# Polarshield_v2_4.net
KiCad netlist of a schematic drawn in EAGLE
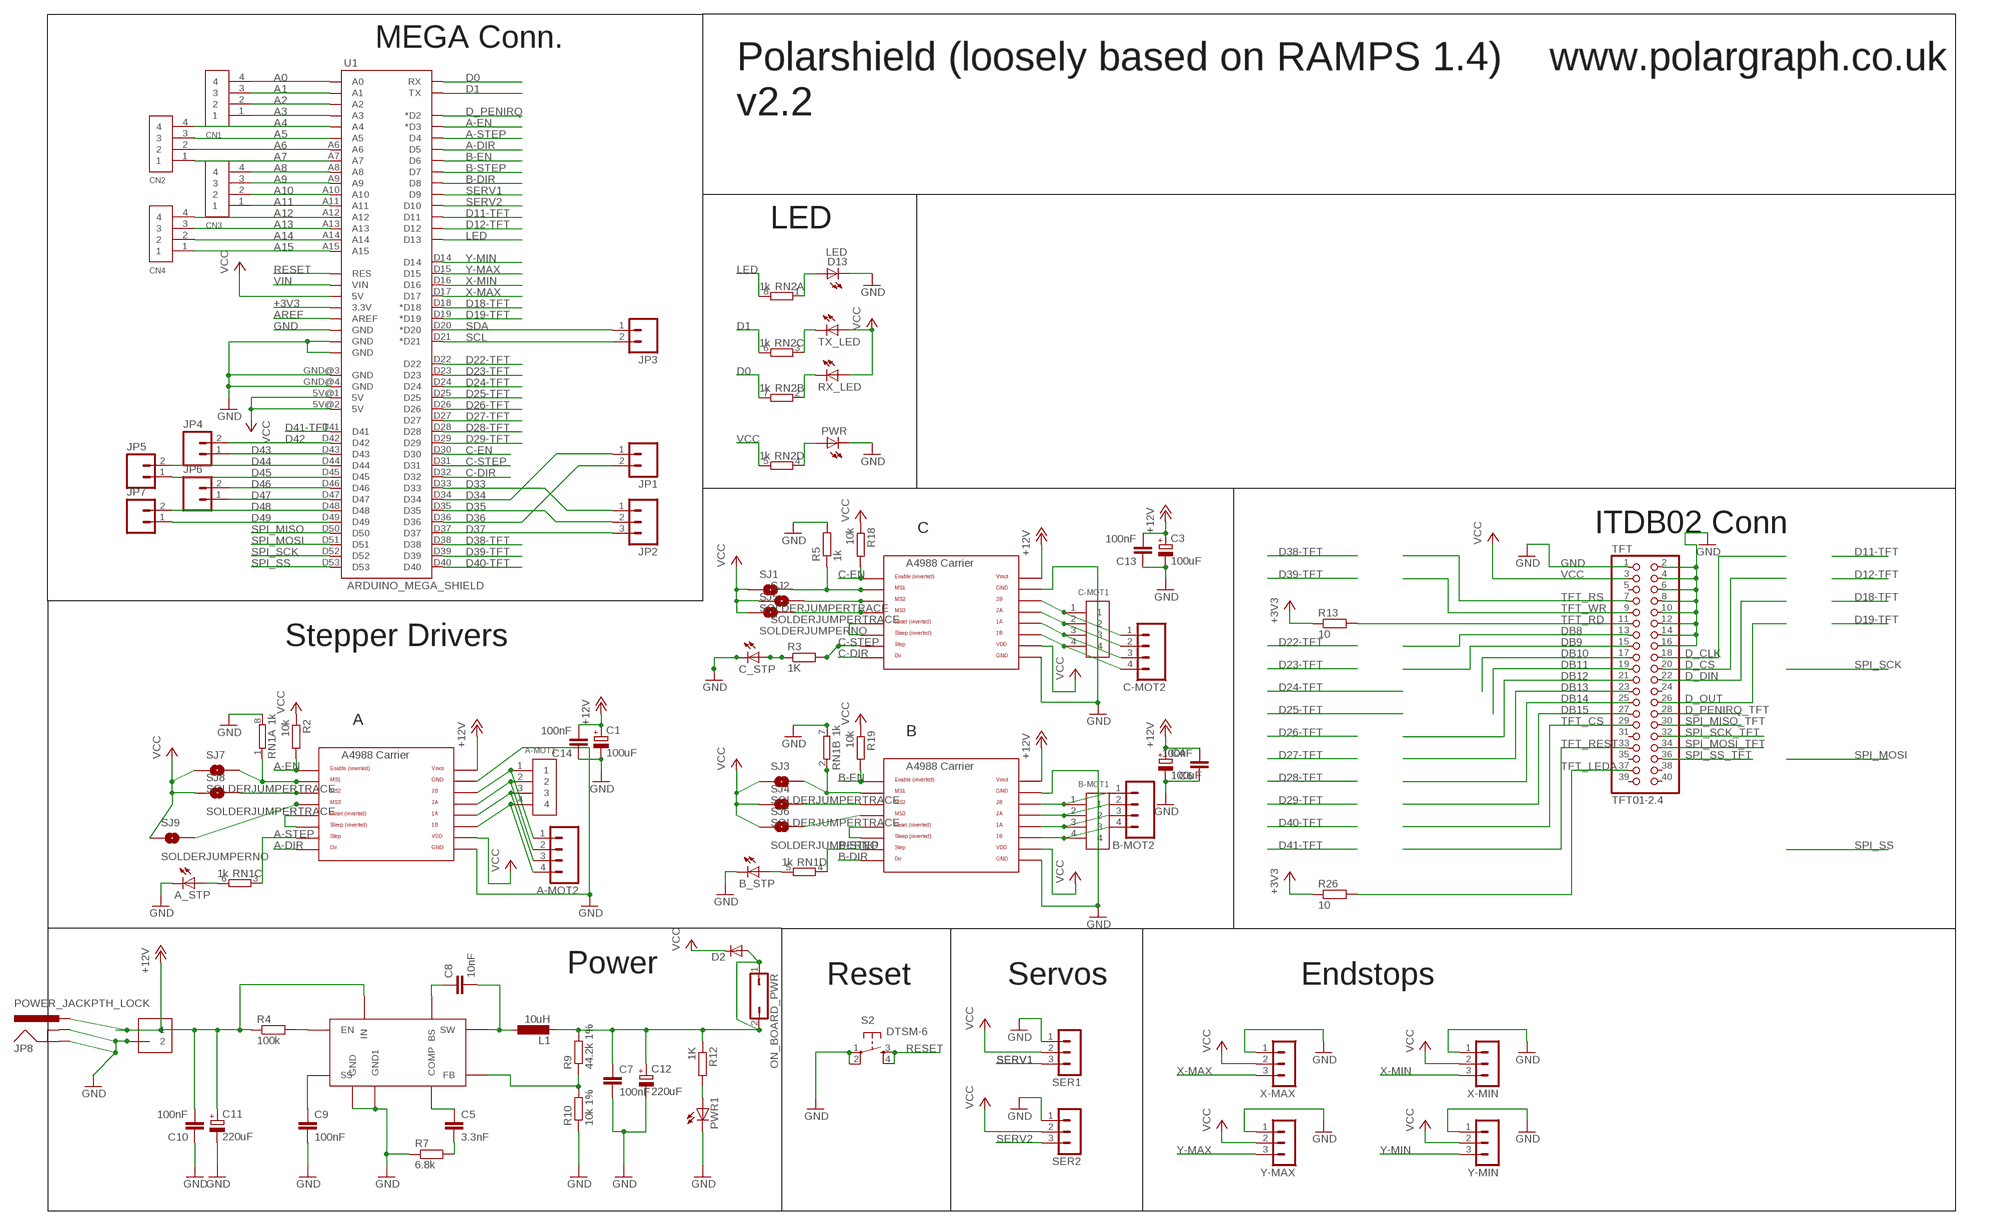
[diagram p0: schematic, sheet 1, part 1 of 2]
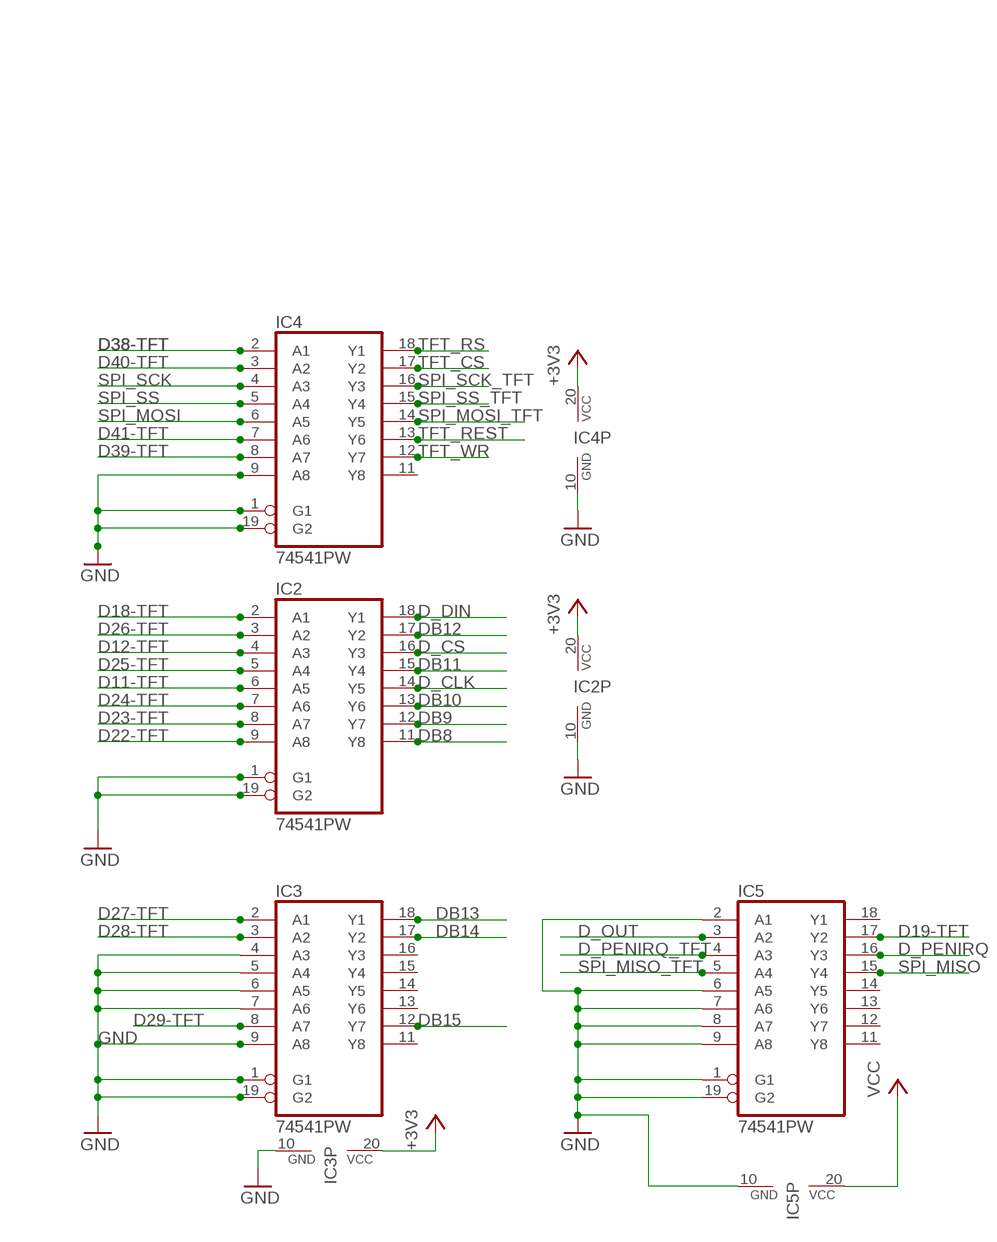
[diagram p1: schematic, sheet 1, part 2 of 2]

(export (version "E")
  (design (tool "Eeschema 10.0.6"))
  (components
    (comp (ref "A-MOT1")
      (value "1X4-BIG")
      (footprint "eagle-import:1X04-BIG")
      (libsource (lib "eagle-import") (part "adafruit_1X4-BIG"))
    )
    (comp (ref "A-MOT2")
      (value "M04SCREW")
      (footprint "eagle-import:SCREWTERMINAL-3.5MM-4")
      (libsource (lib "eagle-import") (part "M04SCREW"))
    )
    (comp (ref "A_STP")
      (value "LEDCHIP-LED0805")
      (footprint "eagle-import:CHIP-LED0805")
      (libsource (lib "eagle-import") (part "LEDCHIP-LED0805"))
    )
    (comp (ref "B-MOT1")
      (value "1X4-BIG")
      (footprint "eagle-import:1X04-BIG")
      (libsource (lib "eagle-import") (part "adafruit_1X4-BIG"))
    )
    (comp (ref "B-MOT2")
      (value "M04SCREW")
      (footprint "eagle-import:SCREWTERMINAL-3.5MM-4")
      (libsource (lib "eagle-import") (part "M04SCREW"))
    )
    (comp (ref "B_STP")
      (value "LEDCHIP-LED0805")
      (footprint "eagle-import:CHIP-LED0805")
      (libsource (lib "eagle-import") (part "LEDCHIP-LED0805"))
    )
    (comp (ref "C-MOT1")
      (value "1X4-BIG")
      (footprint "eagle-import:1X04-BIG")
      (libsource (lib "eagle-import") (part "adafruit_1X4-BIG"))
    )
    (comp (ref "C-MOT2")
      (value "M04SCREW")
      (footprint "eagle-import:SCREWTERMINAL-3.5MM-4")
      (libsource (lib "eagle-import") (part "M04SCREW"))
    )
    (comp (ref "C1")
      (value "100uF")
      (footprint "eagle-import:153CLV-0605")
      (libsource (lib "eagle-import") (part "CPOL-EU153CLV-0605"))
    )
    (comp (ref "C3")
      (value "100uF")
      (footprint "eagle-import:153CLV-0605")
      (libsource (lib "eagle-import") (part "CPOL-EU153CLV-0605"))
    )
    (comp (ref "C4")
      (value "100uF")
      (footprint "eagle-import:153CLV-0605")
      (libsource (lib "eagle-import") (part "CPOL-EU153CLV-0605"))
    )
    (comp (ref "C5")
      (value "3.3nF")
      (footprint "eagle-import:C0805K")
      (libsource (lib "eagle-import") (part "C-EUC0805K"))
    )
    (comp (ref "C6")
      (value "100nF")
      (footprint "eagle-import:C0805")
      (libsource (lib "eagle-import") (part "C-EUC0805"))
    )
    (comp (ref "C7")
      (value "100nF")
      (footprint "eagle-import:C0805K")
      (libsource (lib "eagle-import") (part "C-EUC0805K"))
    )
    (comp (ref "C8")
      (value "10nF")
      (footprint "eagle-import:C0805K")
      (libsource (lib "eagle-import") (part "C-EUC0805K"))
    )
    (comp (ref "C9")
      (value "100nF")
      (footprint "eagle-import:C0805K")
      (libsource (lib "eagle-import") (part "C-EUC0805K"))
    )
    (comp (ref "C10")
      (value "100nF")
      (footprint "eagle-import:C0805K")
      (libsource (lib "eagle-import") (part "C-EUC0805K"))
    )
    (comp (ref "C11")
      (value "220uF")
      (footprint "eagle-import:153CLV-0807")
      (libsource (lib "eagle-import") (part "resistor_CPOL-EU153CLV-0807"))
    )
    (comp (ref "C12")
      (value "220uF")
      (footprint "eagle-import:153CLV-0807")
      (libsource (lib "eagle-import") (part "resistor_CPOL-EU153CLV-0807"))
    )
    (comp (ref "C13")
      (value "100nF")
      (footprint "eagle-import:C0805")
      (libsource (lib "eagle-import") (part "C-EUC0805"))
    )
    (comp (ref "C14")
      (value "100nF")
      (footprint "eagle-import:C0805")
      (libsource (lib "eagle-import") (part "C-EUC0805"))
    )
    (comp (ref "CN1")
      (value "1X4-CLEANBIG")
      (footprint "eagle-import:1X04-CLEANBIG")
      (libsource (lib "eagle-import") (part "1X4-CLEANBIG"))
    )
    (comp (ref "CN2")
      (value "1X4-CLEANBIG")
      (footprint "eagle-import:1X04-CLEANBIG")
      (libsource (lib "eagle-import") (part "1X4-CLEANBIG"))
    )
    (comp (ref "CN3")
      (value "1X4-CLEANBIG")
      (footprint "eagle-import:1X04-CLEANBIG")
      (libsource (lib "eagle-import") (part "1X4-CLEANBIG"))
    )
    (comp (ref "CN4")
      (value "1X4-CLEANBIG")
      (footprint "eagle-import:1X04-CLEANBIG")
      (libsource (lib "eagle-import") (part "1X4-CLEANBIG"))
    )
    (comp (ref "C_STP")
      (value "LEDCHIP-LED0805")
      (footprint "eagle-import:CHIP-LED0805")
      (libsource (lib "eagle-import") (part "LEDCHIP-LED0805"))
    )
    (comp (ref "D2")
      (value "DIODE-DO214BA")
      (footprint "eagle-import:DO214BA")
      (libsource (lib "eagle-import") (part "DIODE-DO214BA"))
    )
    (comp (ref "D13")
      (value "LED")
      (footprint "eagle-import:CHIP-LED0805")
      (libsource (lib "eagle-import") (part "LEDCHIP-LED0805"))
    )
    (comp (ref "IC1")
      (value "MP2307")
      (footprint "eagle-import:SOIC8")
      (libsource (lib "eagle-import") (part "MP2307"))
    )
    (comp (ref "IC2")
      (value "74541PW")
      (footprint "eagle-import:TSSOP20")
      (libsource (lib "eagle-import") (part "74541PW"))
    )
    (comp (ref "IC3")
      (value "74541PW")
      (footprint "eagle-import:TSSOP20")
      (libsource (lib "eagle-import") (part "74541PW"))
    )
    (comp (ref "IC4")
      (value "74541PW")
      (footprint "eagle-import:TSSOP20")
      (libsource (lib "eagle-import") (part "74541PW"))
    )
    (comp (ref "IC5")
      (value "74541PW")
      (footprint "eagle-import:TSSOP20")
      (libsource (lib "eagle-import") (part "74541PW"))
    )
    (comp (ref "J1")
      (value "1X2-3.5MM")
      (footprint "eagle-import:1X2-3.5MM")
      (libsource (lib "eagle-import") (part "1X2-3.5MM"))
    )
    (comp (ref "JP1")
      (value "M021X02_NO_SILK")
      (footprint "eagle-import:1X02_NO_SILK")
      (libsource (lib "eagle-import") (part "M021X02_NO_SILK"))
    )
    (comp (ref "JP2")
      (value "M031X03_NO_SILK")
      (footprint "eagle-import:1X03_NO_SILK")
      (libsource (lib "eagle-import") (part "M031X03_NO_SILK"))
    )
    (comp (ref "JP3")
      (value "M021X02_NO_SILK")
      (footprint "eagle-import:1X02_NO_SILK")
      (libsource (lib "eagle-import") (part "M021X02_NO_SILK"))
    )
    (comp (ref "JP4")
      (value "M021X02_NO_SILK")
      (footprint "eagle-import:1X02_NO_SILK")
      (libsource (lib "eagle-import") (part "M021X02_NO_SILK"))
    )
    (comp (ref "JP5")
      (value "M021X02_NO_SILK")
      (footprint "eagle-import:1X02_NO_SILK")
      (libsource (lib "eagle-import") (part "M021X02_NO_SILK"))
    )
    (comp (ref "JP6")
      (value "M021X02_NO_SILK")
      (footprint "eagle-import:1X02_NO_SILK")
      (libsource (lib "eagle-import") (part "M021X02_NO_SILK"))
    )
    (comp (ref "JP7")
      (value "M021X02_NO_SILK")
      (footprint "eagle-import:1X02_NO_SILK")
      (libsource (lib "eagle-import") (part "M021X02_NO_SILK"))
    )
    (comp (ref "JP8")
      (value "POWER_JACKPTH_LOCK")
      (footprint "eagle-import:POWER_JACK_PTH_LOCK")
      (libsource (lib "eagle-import") (part "POWER_JACKPTH_LOCK"))
    )
    (comp (ref "L1")
      (value "10uH")
      (footprint "eagle-import:PIS2816")
      (libsource (lib "eagle-import") (part "L-EUPIS2816"))
    )
    (comp (ref "ON_BOARD_PWR")
      (value "JP1Q")
      (footprint "eagle-import:JP1")
      (libsource (lib "eagle-import") (part "JP1Q"))
    )
    (comp (ref "PWR")
      (value "LEDCHIP-LED0805")
      (footprint "eagle-import:CHIP-LED0805")
      (libsource (lib "eagle-import") (part "LEDCHIP-LED0805"))
    )
    (comp (ref "PWR1")
      (value "LEDCHIP-LED0805")
      (footprint "eagle-import:CHIP-LED0805")
      (libsource (lib "eagle-import") (part "LEDCHIP-LED0805"))
    )
    (comp (ref "R2")
      (value "10k")
      (footprint "eagle-import:R0805")
      (libsource (lib "eagle-import") (part "R-EU_R0805"))
    )
    (comp (ref "R3")
      (value "1K")
      (footprint "eagle-import:R0805")
      (libsource (lib "eagle-import") (part "R-EU_R0805"))
    )
    (comp (ref "R4")
      (value "100k")
      (footprint "eagle-import:R0805")
      (libsource (lib "eagle-import") (part "resistor_R-EU_R0805"))
    )
    (comp (ref "R5")
      (value "1k")
      (footprint "eagle-import:R0805")
      (libsource (lib "eagle-import") (part "R-EU_R0805"))
    )
    (comp (ref "R7")
      (value "6.8k")
      (footprint "eagle-import:R0805")
      (libsource (lib "eagle-import") (part "resistor_R-EU_R0805"))
    )
    (comp (ref "R9")
      (value "44.2k 1%")
      (footprint "eagle-import:R0805")
      (libsource (lib "eagle-import") (part "resistor_R-EU_R0805"))
    )
    (comp (ref "R10")
      (value "10k 1%")
      (footprint "eagle-import:R0805")
      (libsource (lib "eagle-import") (part "resistor_R-EU_R0805"))
    )
    (comp (ref "R12")
      (value "1K")
      (footprint "eagle-import:R0805")
      (libsource (lib "eagle-import") (part "R-EU_R0805"))
    )
    (comp (ref "R13")
      (value "10")
      (footprint "eagle-import:R0805")
      (libsource (lib "eagle-import") (part "resistor_R-EU_R0805"))
    )
    (comp (ref "R18")
      (value "10k")
      (footprint "eagle-import:R0805")
      (libsource (lib "eagle-import") (part "R-EU_R0805"))
    )
    (comp (ref "R19")
      (value "10k")
      (footprint "eagle-import:R0805")
      (libsource (lib "eagle-import") (part "R-EU_R0805"))
    )
    (comp (ref "R26")
      (value "10")
      (footprint "eagle-import:R0805")
      (libsource (lib "eagle-import") (part "resistor_R-EU_R0805"))
    )
    (comp (ref "RN1")
      (value "1k")
      (footprint "eagle-import:EXBN8V")
      (libsource (lib "eagle-import") (part "4R-NEXBN8V"))
    )
    (comp (ref "RN2")
      (value "1k")
      (footprint "eagle-import:EXBN8V")
      (libsource (lib "eagle-import") (part "4R-NEXBN8V"))
    )
    (comp (ref "RX_LED")
      (value "LEDCHIP-LED0805")
      (footprint "eagle-import:CHIP-LED0805")
      (libsource (lib "eagle-import") (part "LEDCHIP-LED0805"))
    )
    (comp (ref "S2")
      (value "DTSM-6")
      (footprint "eagle-import:DTSM-6")
      (libsource (lib "eagle-import") (part "DTSM-6"))
    )
    (comp (ref "SER1")
      (value "3PIN-HEADER")
      (footprint "eagle-import:3PIN-HEADER")
      (libsource (lib "eagle-import") (part "3PIN-HEADER"))
    )
    (comp (ref "SER2")
      (value "3PIN-HEADER")
      (footprint "eagle-import:3PIN-HEADER")
      (libsource (lib "eagle-import") (part "3PIN-HEADER"))
    )
    (comp (ref "SJ1")
      (value "SOLDERJUMPERTRACE")
      (footprint "eagle-import:SJ_2S-TRACE")
      (libsource (lib "eagle-import") (part "SOLDERJUMPERTRACE"))
    )
    (comp (ref "SJ2")
      (value "SOLDERJUMPERTRACE")
      (footprint "eagle-import:SJ_2S-TRACE")
      (libsource (lib "eagle-import") (part "SOLDERJUMPERTRACE"))
    )
    (comp (ref "SJ3")
      (value "SOLDERJUMPERTRACE")
      (footprint "eagle-import:SJ_2S-TRACE")
      (libsource (lib "eagle-import") (part "SOLDERJUMPERTRACE"))
    )
    (comp (ref "SJ4")
      (value "SOLDERJUMPERTRACE")
      (footprint "eagle-import:SJ_2S-TRACE")
      (libsource (lib "eagle-import") (part "SOLDERJUMPERTRACE"))
    )
    (comp (ref "SJ5")
      (value "SOLDERJUMPERNO")
      (footprint "eagle-import:SJ_2S-NO")
      (libsource (lib "eagle-import") (part "SOLDERJUMPERNO"))
    )
    (comp (ref "SJ6")
      (value "SOLDERJUMPERNO")
      (footprint "eagle-import:SJ_2S-NO")
      (libsource (lib "eagle-import") (part "SOLDERJUMPERNO"))
    )
    (comp (ref "SJ7")
      (value "SOLDERJUMPERTRACE")
      (footprint "eagle-import:SJ_2S-TRACE")
      (libsource (lib "eagle-import") (part "SOLDERJUMPERTRACE"))
    )
    (comp (ref "SJ8")
      (value "SOLDERJUMPERTRACE")
      (footprint "eagle-import:SJ_2S-TRACE")
      (libsource (lib "eagle-import") (part "SOLDERJUMPERTRACE"))
    )
    (comp (ref "SJ9")
      (value "SOLDERJUMPERNO")
      (footprint "eagle-import:SJ_2S-NO")
      (libsource (lib "eagle-import") (part "SOLDERJUMPERNO"))
    )
    (comp (ref "TFT")
      (value "TFT01-2.4")
      (footprint "eagle-import:TFT01-2.4")
      (libsource (lib "eagle-import") (part "TFT01-2.4"))
    )
    (comp (ref "TX_LED")
      (value "LEDCHIP-LED0805")
      (footprint "eagle-import:CHIP-LED0805")
      (libsource (lib "eagle-import") (part "LEDCHIP-LED0805"))
    )
    (comp (ref "U$1")
      (value "A4988BREAKOUT")
      (footprint "eagle-import:A4988BREAKOUT")
      (libsource (lib "eagle-import") (part "A4988BREAKOUT"))
    )
    (comp (ref "U$6")
      (value "A4988BREAKOUT")
      (footprint "eagle-import:A4988BREAKOUT")
      (libsource (lib "eagle-import") (part "A4988BREAKOUT"))
    )
    (comp (ref "U$7")
      (value "A4988BREAKOUT")
      (footprint "eagle-import:A4988BREAKOUT")
      (libsource (lib "eagle-import") (part "A4988BREAKOUT"))
    )
    (comp (ref "U1")
      (value "ARDUINO_MEGA_SHIELD")
      (footprint "eagle-import:ARDUINO_MEGA_SHIELD")
      (libsource (lib "eagle-import") (part "ARDUINO_MEGA_SHIELD"))
    )
    (comp (ref "X-MAX")
      (value "3PIN-HEADER")
      (footprint "eagle-import:3PIN-HEADER")
      (libsource (lib "eagle-import") (part "3PIN-HEADER"))
    )
    (comp (ref "X-MIN")
      (value "3PIN-HEADER")
      (footprint "eagle-import:3PIN-HEADER")
      (libsource (lib "eagle-import") (part "3PIN-HEADER"))
    )
    (comp (ref "Y-MAX")
      (value "3PIN-HEADER")
      (footprint "eagle-import:3PIN-HEADER")
      (libsource (lib "eagle-import") (part "3PIN-HEADER"))
    )
    (comp (ref "Y-MIN")
      (value "3PIN-HEADER")
      (footprint "eagle-import:3PIN-HEADER")
      (libsource (lib "eagle-import") (part "3PIN-HEADER"))
    )
  )
  (nets
    (net (code "1") (name "+3V3") (class "Default")
      (node (ref "IC2") (pin "20") (pinfunction "VCC_20") (pintype "power_in"))
      (node (ref "IC3") (pin "20") (pinfunction "VCC_20") (pintype "power_in"))
      (node (ref "IC4") (pin "20") (pinfunction "VCC_20") (pintype "power_in"))
      (node (ref "R13") (pin "1") (pinfunction "1_1") (pintype "passive"))
      (node (ref "R26") (pin "1") (pinfunction "1_1") (pintype "passive"))
      (node (ref "U1") (pin "3.3V") (pinfunction "3.3V_3.3V") (pintype "bidirectional"))
    )
    (net (code "2") (name "+12V") (class "Default")
      (node (ref "C1") (pin "+") (pinfunction "+_+") (pintype "passive"))
      (node (ref "C10") (pin "2") (pinfunction "2_2") (pintype "passive"))
      (node (ref "C11") (pin "+") (pinfunction "+_+") (pintype "passive"))
      (node (ref "C13") (pin "2") (pinfunction "2_2") (pintype "passive"))
      (node (ref "C14") (pin "2") (pinfunction "2_2") (pintype "passive"))
      (node (ref "C3") (pin "+") (pinfunction "+_+") (pintype "passive"))
      (node (ref "C4") (pin "+") (pinfunction "+_+") (pintype "passive"))
      (node (ref "C6") (pin "2") (pinfunction "2_2") (pintype "passive"))
      (node (ref "IC1") (pin "IN") (pinfunction "IN_IN") (pintype "bidirectional"))
      (node (ref "J1") (pin "1") (pinfunction "1_1") (pintype "passive"))
      (node (ref "JP8") (pin "PWR") (pinfunction "PWR_PWR") (pintype "bidirectional"))
      (node (ref "R4") (pin "1") (pinfunction "1_1") (pintype "passive"))
      (node (ref "U$1") (pin "VMOT") (pinfunction "VMOT_VMOT") (pintype "power_in"))
      (node (ref "U$6") (pin "VMOT") (pinfunction "VMOT_VMOT") (pintype "power_in"))
      (node (ref "U$7") (pin "VMOT") (pinfunction "VMOT_VMOT") (pintype "power_in"))
    )
    (net (code "3") (name "/A-DIR") (class "Default")
      (node (ref "U$1") (pin "DIR") (pinfunction "DIR_DIR") (pintype "input"))
      (node (ref "U1") (pin "D5") (pinfunction "D5_D5") (pintype "bidirectional"))
    )
    (net (code "4") (name "/A-EN") (class "Default")
      (node (ref "R2") (pin "2") (pinfunction "2_2") (pintype "passive"))
      (node (ref "U$1") (pin "EN") (pinfunction "EN_EN") (pintype "input"))
      (node (ref "U1") (pin "D3") (pinfunction "*D3_D3") (pintype "bidirectional"))
    )
    (net (code "5") (name "/A-STEP") (class "Default")
      (node (ref "RN1") (pin "3") (pinfunction "1_3") (pintype "passive"))
      (node (ref "U$1") (pin "STEP") (pinfunction "STEP_STEP") (pintype "input"))
      (node (ref "U1") (pin "D4") (pinfunction "D4_D4") (pintype "bidirectional"))
    )
    (net (code "6") (name "/A0") (class "Default")
      (node (ref "CN1") (pin "4") (pinfunction "4_4") (pintype "bidirectional"))
      (node (ref "U1") (pin "A0") (pinfunction "A0_A0") (pintype "bidirectional"))
    )
    (net (code "7") (name "/A1") (class "Default")
      (node (ref "CN1") (pin "3") (pinfunction "3_3") (pintype "bidirectional"))
      (node (ref "U1") (pin "A1") (pinfunction "A1_A1") (pintype "bidirectional"))
    )
    (net (code "8") (name "/A2") (class "Default")
      (node (ref "CN1") (pin "2") (pinfunction "2_2") (pintype "bidirectional"))
      (node (ref "U1") (pin "A2") (pinfunction "A2_A2") (pintype "bidirectional"))
    )
    (net (code "9") (name "/A3") (class "Default")
      (node (ref "CN1") (pin "1") (pinfunction "1_1") (pintype "bidirectional"))
      (node (ref "U1") (pin "A3") (pinfunction "A3_A3") (pintype "bidirectional"))
    )
    (net (code "10") (name "/A4") (class "Default")
      (node (ref "CN2") (pin "4") (pinfunction "4_4") (pintype "bidirectional"))
      (node (ref "U1") (pin "A4") (pinfunction "A4_A4") (pintype "bidirectional"))
    )
    (net (code "11") (name "/A5") (class "Default")
      (node (ref "CN2") (pin "3") (pinfunction "3_3") (pintype "bidirectional"))
      (node (ref "U1") (pin "A5") (pinfunction "A5_A5") (pintype "bidirectional"))
    )
    (net (code "12") (name "/A6") (class "Default")
      (node (ref "CN2") (pin "2") (pinfunction "2_2") (pintype "bidirectional"))
      (node (ref "U1") (pin "A6") (pinfunction "A6_A6") (pintype "bidirectional"))
    )
    (net (code "13") (name "/A7") (class "Default")
      (node (ref "CN2") (pin "1") (pinfunction "1_1") (pintype "bidirectional"))
      (node (ref "U1") (pin "A7") (pinfunction "A7_A7") (pintype "bidirectional"))
    )
    (net (code "14") (name "/A8") (class "Default")
      (node (ref "CN3") (pin "4") (pinfunction "4_4") (pintype "bidirectional"))
      (node (ref "U1") (pin "A8") (pinfunction "A8_A8") (pintype "bidirectional"))
    )
    (net (code "15") (name "/A9") (class "Default")
      (node (ref "CN3") (pin "3") (pinfunction "3_3") (pintype "bidirectional"))
      (node (ref "U1") (pin "A9") (pinfunction "A9_A9") (pintype "bidirectional"))
    )
    (net (code "16") (name "/A10") (class "Default")
      (node (ref "CN3") (pin "2") (pinfunction "2_2") (pintype "bidirectional"))
      (node (ref "U1") (pin "A10") (pinfunction "A10_A10") (pintype "bidirectional"))
    )
    (net (code "17") (name "/A11") (class "Default")
      (node (ref "CN3") (pin "1") (pinfunction "1_1") (pintype "bidirectional"))
      (node (ref "U1") (pin "A11") (pinfunction "A11_A11") (pintype "bidirectional"))
    )
    (net (code "18") (name "/A12") (class "Default")
      (node (ref "CN4") (pin "4") (pinfunction "4_4") (pintype "bidirectional"))
      (node (ref "U1") (pin "A12") (pinfunction "A12_A12") (pintype "bidirectional"))
    )
    (net (code "19") (name "/A13") (class "Default")
      (node (ref "CN4") (pin "3") (pinfunction "3_3") (pintype "bidirectional"))
      (node (ref "U1") (pin "A13") (pinfunction "A13_A13") (pintype "bidirectional"))
    )
    (net (code "20") (name "/A14") (class "Default")
      (node (ref "CN4") (pin "2") (pinfunction "2_2") (pintype "bidirectional"))
      (node (ref "U1") (pin "A14") (pinfunction "A14_A14") (pintype "bidirectional"))
    )
    (net (code "21") (name "/A15") (class "Default")
      (node (ref "CN4") (pin "1") (pinfunction "1_1") (pintype "bidirectional"))
      (node (ref "U1") (pin "A15") (pinfunction "A15_A15") (pintype "bidirectional"))
    )
    (net (code "22") (name "/AREF") (class "Default")
      (node (ref "U1") (pin "AREF") (pinfunction "AREF_AREF") (pintype "bidirectional"))
    )
    (net (code "23") (name "/B-DIR") (class "Default")
      (node (ref "U$7") (pin "DIR") (pinfunction "DIR_DIR") (pintype "input"))
      (node (ref "U1") (pin "D8") (pinfunction "D8_D8") (pintype "bidirectional"))
    )
    (net (code "24") (name "/B-EN") (class "Default")
      (node (ref "R19") (pin "2") (pinfunction "2_2") (pintype "passive"))
      (node (ref "U$7") (pin "EN") (pinfunction "EN_EN") (pintype "input"))
      (node (ref "U1") (pin "D6") (pinfunction "D6_D6") (pintype "bidirectional"))
    )
    (net (code "25") (name "/B-STEP") (class "Default")
      (node (ref "RN1") (pin "4") (pinfunction "1_4") (pintype "passive"))
      (node (ref "U$7") (pin "STEP") (pinfunction "STEP_STEP") (pintype "input"))
      (node (ref "U1") (pin "D7") (pinfunction "D7_D7") (pintype "bidirectional"))
    )
    (net (code "26") (name "/C-DIR") (class "Default")
      (node (ref "U$6") (pin "DIR") (pinfunction "DIR_DIR") (pintype "input"))
      (node (ref "U1") (pin "D32") (pinfunction "D32_D32") (pintype "bidirectional"))
    )
    (net (code "27") (name "/C-EN") (class "Default")
      (node (ref "R18") (pin "2") (pinfunction "2_2") (pintype "passive"))
      (node (ref "U$6") (pin "EN") (pinfunction "EN_EN") (pintype "input"))
      (node (ref "U1") (pin "D30") (pinfunction "D30_D30") (pintype "bidirectional"))
    )
    (net (code "28") (name "/C-STEP") (class "Default")
      (node (ref "R3") (pin "2") (pinfunction "2_2") (pintype "passive"))
      (node (ref "U$6") (pin "STEP") (pinfunction "STEP_STEP") (pintype "input"))
      (node (ref "U1") (pin "D31") (pinfunction "D31_D31") (pintype "bidirectional"))
    )
    (net (code "29") (name "/D0") (class "Default")
      (node (ref "RN2") (pin "7") (pinfunction "2_7") (pintype "passive"))
      (node (ref "U1") (pin "RX") (pinfunction "RX_RX") (pintype "bidirectional"))
    )
    (net (code "30") (name "/D1") (class "Default")
      (node (ref "RN2") (pin "6") (pinfunction "2_6") (pintype "passive"))
      (node (ref "U1") (pin "TX") (pinfunction "TX_TX") (pintype "bidirectional"))
    )
    (net (code "31") (name "/D11-TFT") (class "Default")
      (node (ref "IC2") (pin "6") (pinfunction "A5_6") (pintype "input"))
      (node (ref "U1") (pin "D11") (pinfunction "D11_D11") (pintype "bidirectional"))
    )
    (net (code "32") (name "/D12-TFT") (class "Default")
      (node (ref "IC2") (pin "4") (pinfunction "A3_4") (pintype "input"))
      (node (ref "U1") (pin "D12") (pinfunction "D12_D12") (pintype "bidirectional"))
    )
    (net (code "33") (name "/D18-TFT") (class "Default")
      (node (ref "IC2") (pin "2") (pinfunction "A1_2") (pintype "input"))
      (node (ref "U1") (pin "D18") (pinfunction "*D18_D18") (pintype "bidirectional"))
    )
    (net (code "34") (name "/D19-TFT") (class "Default")
      (node (ref "IC5") (pin "17") (pinfunction "Y2_17") (pintype "tri_state"))
      (node (ref "U1") (pin "D19") (pinfunction "*D19_D19") (pintype "bidirectional"))
    )
    (net (code "35") (name "/D22-TFT") (class "Default")
      (node (ref "IC2") (pin "9") (pinfunction "A8_9") (pintype "input"))
      (node (ref "U1") (pin "D22") (pinfunction "D22_D22") (pintype "bidirectional"))
    )
    (net (code "36") (name "/D23-TFT") (class "Default")
      (node (ref "IC2") (pin "8") (pinfunction "A7_8") (pintype "input"))
      (node (ref "U1") (pin "D23") (pinfunction "D23_D23") (pintype "bidirectional"))
    )
    (net (code "37") (name "/D24-TFT") (class "Default")
      (node (ref "IC2") (pin "7") (pinfunction "A6_7") (pintype "input"))
      (node (ref "U1") (pin "D24") (pinfunction "D24_D24") (pintype "bidirectional"))
    )
    (net (code "38") (name "/D25-TFT") (class "Default")
      (node (ref "IC2") (pin "5") (pinfunction "A4_5") (pintype "input"))
      (node (ref "U1") (pin "D25") (pinfunction "D25_D25") (pintype "bidirectional"))
    )
    (net (code "39") (name "/D26-TFT") (class "Default")
      (node (ref "IC2") (pin "3") (pinfunction "A2_3") (pintype "input"))
      (node (ref "U1") (pin "D26") (pinfunction "D26_D26") (pintype "bidirectional"))
    )
    (net (code "40") (name "/D27-TFT") (class "Default")
      (node (ref "IC3") (pin "2") (pinfunction "A1_2") (pintype "input"))
      (node (ref "U1") (pin "D27") (pinfunction "D27_D27") (pintype "bidirectional"))
    )
    (net (code "41") (name "/D28-TFT") (class "Default")
      (node (ref "IC3") (pin "3") (pinfunction "A2_3") (pintype "input"))
      (node (ref "U1") (pin "D28") (pinfunction "D28_D28") (pintype "bidirectional"))
    )
    (net (code "42") (name "/D29-TFT") (class "Default")
      (node (ref "IC3") (pin "8") (pinfunction "A7_8") (pintype "input"))
      (node (ref "U1") (pin "D29") (pinfunction "D29_D29") (pintype "bidirectional"))
    )
    (net (code "43") (name "/D33") (class "Default")
      (node (ref "JP2") (pin "1") (pinfunction "1_1") (pintype "passive"))
      (node (ref "U1") (pin "D33") (pinfunction "D33_D33") (pintype "bidirectional"))
    )
    (net (code "44") (name "/D34") (class "Default")
      (node (ref "JP1") (pin "1") (pinfunction "1_1") (pintype "passive"))
      (node (ref "U1") (pin "D34") (pinfunction "D34_D34") (pintype "bidirectional"))
    )
    (net (code "45") (name "/D35") (class "Default")
      (node (ref "JP2") (pin "2") (pinfunction "2_2") (pintype "passive"))
      (node (ref "U1") (pin "D35") (pinfunction "D35_D35") (pintype "bidirectional"))
    )
    (net (code "46") (name "/D36") (class "Default")
      (node (ref "JP1") (pin "2") (pinfunction "2_2") (pintype "passive"))
      (node (ref "U1") (pin "D36") (pinfunction "D36_D36") (pintype "bidirectional"))
    )
    (net (code "47") (name "/D37") (class "Default")
      (node (ref "JP2") (pin "3") (pinfunction "3_3") (pintype "passive"))
      (node (ref "U1") (pin "D37") (pinfunction "D37_D37") (pintype "bidirectional"))
    )
    (net (code "48") (name "/D38-TFT") (class "Default")
      (node (ref "IC4") (pin "2") (pinfunction "A1_2") (pintype "input"))
      (node (ref "U1") (pin "D38") (pinfunction "D38_D38") (pintype "bidirectional"))
    )
    (net (code "49") (name "/D39-TFT") (class "Default")
      (node (ref "IC4") (pin "8") (pinfunction "A7_8") (pintype "input"))
      (node (ref "U1") (pin "D39") (pinfunction "D39_D39") (pintype "bidirectional"))
    )
    (net (code "50") (name "/D40-TFT") (class "Default")
      (node (ref "IC4") (pin "3") (pinfunction "A2_3") (pintype "input"))
      (node (ref "U1") (pin "D40") (pinfunction "D40_D40") (pintype "bidirectional"))
    )
    (net (code "51") (name "/D41-TFT") (class "Default")
      (node (ref "IC4") (pin "7") (pinfunction "A6_7") (pintype "input"))
      (node (ref "U1") (pin "D41") (pinfunction "D41_D41") (pintype "bidirectional"))
    )
    (net (code "52") (name "/D42") (class "Default")
      (node (ref "JP4") (pin "2") (pinfunction "2_2") (pintype "passive"))
      (node (ref "U1") (pin "D42") (pinfunction "D42_D42") (pintype "bidirectional"))
    )
    (net (code "53") (name "/D43") (class "Default")
      (node (ref "JP4") (pin "1") (pinfunction "1_1") (pintype "passive"))
      (node (ref "U1") (pin "D43") (pinfunction "D43_D43") (pintype "bidirectional"))
    )
    (net (code "54") (name "/D44") (class "Default")
      (node (ref "JP5") (pin "2") (pinfunction "2_2") (pintype "passive"))
      (node (ref "U1") (pin "D44") (pinfunction "D44_D44") (pintype "bidirectional"))
    )
    (net (code "55") (name "/D45") (class "Default")
      (node (ref "JP5") (pin "1") (pinfunction "1_1") (pintype "passive"))
      (node (ref "U1") (pin "D45") (pinfunction "D45_D45") (pintype "bidirectional"))
    )
    (net (code "56") (name "/D46") (class "Default")
      (node (ref "JP6") (pin "2") (pinfunction "2_2") (pintype "passive"))
      (node (ref "U1") (pin "D46") (pinfunction "D46_D46") (pintype "bidirectional"))
    )
    (net (code "57") (name "/D47") (class "Default")
      (node (ref "JP6") (pin "1") (pinfunction "1_1") (pintype "passive"))
      (node (ref "U1") (pin "D47") (pinfunction "D47_D47") (pintype "bidirectional"))
    )
    (net (code "58") (name "/D48") (class "Default")
      (node (ref "JP7") (pin "2") (pinfunction "2_2") (pintype "passive"))
      (node (ref "U1") (pin "D48") (pinfunction "D48_D48") (pintype "bidirectional"))
    )
    (net (code "59") (name "/D49") (class "Default")
      (node (ref "JP7") (pin "1") (pinfunction "1_1") (pintype "passive"))
      (node (ref "U1") (pin "D49") (pinfunction "D49_D49") (pintype "bidirectional"))
    )
    (net (code "60") (name "/DB8") (class "Default")
      (node (ref "IC2") (pin "11") (pinfunction "Y8_11") (pintype "tri_state"))
      (node (ref "TFT") (pin "13") (pinfunction "13_13") (pintype "passive"))
    )
    (net (code "61") (name "/DB9") (class "Default")
      (node (ref "IC2") (pin "12") (pinfunction "Y7_12") (pintype "tri_state"))
      (node (ref "TFT") (pin "15") (pinfunction "15_15") (pintype "passive"))
    )
    (net (code "62") (name "/DB10") (class "Default")
      (node (ref "IC2") (pin "13") (pinfunction "Y6_13") (pintype "tri_state"))
      (node (ref "TFT") (pin "17") (pinfunction "17_17") (pintype "passive"))
    )
    (net (code "63") (name "/DB11") (class "Default")
      (node (ref "IC2") (pin "15") (pinfunction "Y4_15") (pintype "tri_state"))
      (node (ref "TFT") (pin "19") (pinfunction "19_19") (pintype "passive"))
    )
    (net (code "64") (name "/DB12") (class "Default")
      (node (ref "IC2") (pin "17") (pinfunction "Y2_17") (pintype "tri_state"))
      (node (ref "TFT") (pin "21") (pinfunction "21_21") (pintype "passive"))
    )
    (net (code "65") (name "/DB13") (class "Default")
      (node (ref "IC3") (pin "18") (pinfunction "Y1_18") (pintype "tri_state"))
      (node (ref "TFT") (pin "23") (pinfunction "23_23") (pintype "passive"))
    )
    (net (code "66") (name "/DB14") (class "Default")
      (node (ref "IC3") (pin "17") (pinfunction "Y2_17") (pintype "tri_state"))
      (node (ref "TFT") (pin "25") (pinfunction "25_25") (pintype "passive"))
    )
    (net (code "67") (name "/DB15") (class "Default")
      (node (ref "IC3") (pin "12") (pinfunction "Y7_12") (pintype "tri_state"))
      (node (ref "TFT") (pin "27") (pinfunction "27_27") (pintype "passive"))
    )
    (net (code "68") (name "/D_CLK") (class "Default")
      (node (ref "IC2") (pin "14") (pinfunction "Y5_14") (pintype "tri_state"))
      (node (ref "TFT") (pin "18") (pinfunction "18_18") (pintype "passive"))
    )
    (net (code "69") (name "/D_CS") (class "Default")
      (node (ref "IC2") (pin "16") (pinfunction "Y3_16") (pintype "tri_state"))
      (node (ref "TFT") (pin "20") (pinfunction "20_20") (pintype "passive"))
    )
    (net (code "70") (name "/D_DIN") (class "Default")
      (node (ref "IC2") (pin "18") (pinfunction "Y1_18") (pintype "tri_state"))
      (node (ref "TFT") (pin "22") (pinfunction "22_22") (pintype "passive"))
    )
    (net (code "71") (name "/D_OUT") (class "Default")
      (node (ref "IC5") (pin "3") (pinfunction "A2_3") (pintype "input"))
      (node (ref "TFT") (pin "26") (pinfunction "26_26") (pintype "passive"))
    )
    (net (code "72") (name "/D_PENIRQ") (class "Default")
      (node (ref "IC5") (pin "16") (pinfunction "Y3_16") (pintype "tri_state"))
      (node (ref "U1") (pin "D2") (pinfunction "*D2_D2") (pintype "bidirectional"))
    )
    (net (code "73") (name "/D_PENIRQ_TFT") (class "Default")
      (node (ref "IC5") (pin "4") (pinfunction "A3_4") (pintype "input"))
      (node (ref "TFT") (pin "28") (pinfunction "28_28") (pintype "passive"))
    )
    (net (code "74") (name "/LED") (class "Default")
      (node (ref "RN2") (pin "8") (pinfunction "2_8") (pintype "passive"))
      (node (ref "U1") (pin "D13") (pinfunction "D13_D13") (pintype "bidirectional"))
    )
    (net (code "75") (name "/RESET") (class "Default")
      (node (ref "S2") (pin "3") (pinfunction "3_3") (pintype "passive"))
      (node (ref "S2") (pin "4") (pinfunction "4_4") (pintype "passive"))
      (node (ref "U1") (pin "RES") (pinfunction "RES_RES") (pintype "bidirectional"))
    )
    (net (code "76") (name "/SCL") (class "Default")
      (node (ref "JP3") (pin "2") (pinfunction "2_2") (pintype "passive"))
      (node (ref "U1") (pin "D21") (pinfunction "*D21_D21") (pintype "bidirectional"))
    )
    (net (code "77") (name "/SDA") (class "Default")
      (node (ref "JP3") (pin "1") (pinfunction "1_1") (pintype "passive"))
      (node (ref "U1") (pin "D20") (pinfunction "*D20_D20") (pintype "bidirectional"))
    )
    (net (code "78") (name "/SERV1") (class "Default")
      (node (ref "SER1") (pin "3") (pinfunction "3_3") (pintype "passive"))
      (node (ref "U1") (pin "D9") (pinfunction "D9_D9") (pintype "bidirectional"))
    )
    (net (code "79") (name "/SERV2") (class "Default")
      (node (ref "SER2") (pin "3") (pinfunction "3_3") (pintype "passive"))
      (node (ref "U1") (pin "D10") (pinfunction "D10_D10") (pintype "bidirectional"))
    )
    (net (code "80") (name "/SPI_MISO") (class "Default")
      (node (ref "IC5") (pin "15") (pinfunction "Y4_15") (pintype "tri_state"))
      (node (ref "U1") (pin "D50") (pinfunction "D50_D50") (pintype "bidirectional"))
    )
    (net (code "81") (name "/SPI_MISO_TFT") (class "Default")
      (node (ref "IC5") (pin "5") (pinfunction "A4_5") (pintype "input"))
      (node (ref "TFT") (pin "30") (pinfunction "30_30") (pintype "passive"))
    )
    (net (code "82") (name "/SPI_MOSI") (class "Default")
      (node (ref "IC4") (pin "6") (pinfunction "A5_6") (pintype "input"))
      (node (ref "U1") (pin "D51") (pinfunction "D51_D51") (pintype "bidirectional"))
    )
    (net (code "83") (name "/SPI_MOSI_TFT") (class "Default")
      (node (ref "IC4") (pin "14") (pinfunction "Y5_14") (pintype "tri_state"))
      (node (ref "TFT") (pin "34") (pinfunction "34_34") (pintype "passive"))
    )
    (net (code "84") (name "/SPI_SCK") (class "Default")
      (node (ref "IC4") (pin "4") (pinfunction "A3_4") (pintype "input"))
      (node (ref "U1") (pin "D52") (pinfunction "D52_D52") (pintype "bidirectional"))
    )
    (net (code "85") (name "/SPI_SCK_TFT") (class "Default")
      (node (ref "IC4") (pin "16") (pinfunction "Y3_16") (pintype "tri_state"))
      (node (ref "TFT") (pin "32") (pinfunction "32_32") (pintype "passive"))
    )
    (net (code "86") (name "/SPI_SS") (class "Default")
      (node (ref "IC4") (pin "5") (pinfunction "A4_5") (pintype "input"))
      (node (ref "U1") (pin "D53") (pinfunction "D53_D53") (pintype "bidirectional"))
    )
    (net (code "87") (name "/SPI_SS_TFT") (class "Default")
      (node (ref "IC4") (pin "15") (pinfunction "Y4_15") (pintype "tri_state"))
      (node (ref "TFT") (pin "36") (pinfunction "36_36") (pintype "passive"))
    )
    (net (code "88") (name "/TFT_CS") (class "Default")
      (node (ref "IC4") (pin "17") (pinfunction "Y2_17") (pintype "tri_state"))
      (node (ref "TFT") (pin "29") (pinfunction "29_29") (pintype "passive"))
    )
    (net (code "89") (name "/TFT_LEDA") (class "Default")
      (node (ref "R26") (pin "2") (pinfunction "2_2") (pintype "passive"))
      (node (ref "TFT") (pin "37") (pinfunction "37_37") (pintype "passive"))
    )
    (net (code "90") (name "/TFT_RD") (class "Default")
      (node (ref "R13") (pin "2") (pinfunction "2_2") (pintype "passive"))
      (node (ref "TFT") (pin "11") (pinfunction "11_11") (pintype "passive"))
    )
    (net (code "91") (name "/TFT_REST") (class "Default")
      (node (ref "IC4") (pin "13") (pinfunction "Y6_13") (pintype "tri_state"))
      (node (ref "TFT") (pin "33") (pinfunction "33_33") (pintype "passive"))
    )
    (net (code "92") (name "/TFT_RS") (class "Default")
      (node (ref "IC4") (pin "18") (pinfunction "Y1_18") (pintype "tri_state"))
      (node (ref "TFT") (pin "7") (pinfunction "7_7") (pintype "passive"))
    )
    (net (code "93") (name "/TFT_WR") (class "Default")
      (node (ref "IC4") (pin "12") (pinfunction "Y7_12") (pintype "tri_state"))
      (node (ref "TFT") (pin "9") (pinfunction "9_9") (pintype "passive"))
    )
    (net (code "94") (name "/VIN") (class "Default")
      (node (ref "U1") (pin "VIN") (pinfunction "VIN_VIN") (pintype "bidirectional"))
    )
    (net (code "95") (name "/X-MAX") (class "Default")
      (node (ref "U1") (pin "D17") (pinfunction "D17_D17") (pintype "bidirectional"))
      (node (ref "X-MAX") (pin "3") (pinfunction "3_3") (pintype "passive"))
    )
    (net (code "96") (name "/X-MIN") (class "Default")
      (node (ref "U1") (pin "D16") (pinfunction "D16_D16") (pintype "bidirectional"))
      (node (ref "X-MIN") (pin "3") (pinfunction "3_3") (pintype "passive"))
    )
    (net (code "97") (name "/Y-MAX") (class "Default")
      (node (ref "U1") (pin "D15") (pinfunction "D15_D15") (pintype "bidirectional"))
      (node (ref "Y-MAX") (pin "3") (pinfunction "3_3") (pintype "passive"))
    )
    (net (code "98") (name "/Y-MIN") (class "Default")
      (node (ref "U1") (pin "D14") (pinfunction "D14_D14") (pintype "bidirectional"))
      (node (ref "Y-MIN") (pin "3") (pinfunction "3_3") (pintype "passive"))
    )
    (net (code "99") (name "GND") (class "Default")
      (node (ref "A_STP") (pin "C") (pinfunction "C_C") (pintype "passive"))
      (node (ref "B_STP") (pin "C") (pinfunction "C_C") (pintype "passive"))
      (node (ref "C1") (pin "-") (pinfunction "-_-") (pintype "passive"))
      (node (ref "C10") (pin "1") (pinfunction "1_1") (pintype "passive"))
      (node (ref "C11") (pin "-") (pinfunction "-_-") (pintype "passive"))
      (node (ref "C12") (pin "-") (pinfunction "-_-") (pintype "passive"))
      (node (ref "C13") (pin "1") (pinfunction "1_1") (pintype "passive"))
      (node (ref "C14") (pin "1") (pinfunction "1_1") (pintype "passive"))
      (node (ref "C3") (pin "-") (pinfunction "-_-") (pintype "passive"))
      (node (ref "C4") (pin "-") (pinfunction "-_-") (pintype "passive"))
      (node (ref "C6") (pin "1") (pinfunction "1_1") (pintype "passive"))
      (node (ref "C7") (pin "2") (pinfunction "2_2") (pintype "passive"))
      (node (ref "C9") (pin "2") (pinfunction "2_2") (pintype "passive"))
      (node (ref "C_STP") (pin "C") (pinfunction "C_C") (pintype "passive"))
      (node (ref "D13") (pin "C") (pinfunction "C_C") (pintype "passive"))
      (node (ref "IC1") (pin "GND") (pinfunction "GND_GND") (pintype "bidirectional"))
      (node (ref "IC1") (pin "GND1") (pinfunction "GND1_GND1") (pintype "bidirectional"))
      (node (ref "IC2") (pin "1") (pinfunction "G1_1") (pintype "input"))
      (node (ref "IC2") (pin "10") (pinfunction "GND_10") (pintype "power_in"))
      (node (ref "IC2") (pin "19") (pinfunction "G2_19") (pintype "input"))
      (node (ref "IC3") (pin "1") (pinfunction "G1_1") (pintype "input"))
      (node (ref "IC3") (pin "10") (pinfunction "GND_10") (pintype "power_in"))
      (node (ref "IC3") (pin "19") (pinfunction "G2_19") (pintype "input"))
      (node (ref "IC3") (pin "4") (pinfunction "A3_4") (pintype "input"))
      (node (ref "IC3") (pin "5") (pinfunction "A4_5") (pintype "input"))
      (node (ref "IC3") (pin "6") (pinfunction "A5_6") (pintype "input"))
      (node (ref "IC3") (pin "7") (pinfunction "A6_7") (pintype "input"))
      (node (ref "IC3") (pin "9") (pinfunction "A8_9") (pintype "input"))
      (node (ref "IC4") (pin "1") (pinfunction "G1_1") (pintype "input"))
      (node (ref "IC4") (pin "10") (pinfunction "GND_10") (pintype "power_in"))
      (node (ref "IC4") (pin "19") (pinfunction "G2_19") (pintype "input"))
      (node (ref "IC4") (pin "9") (pinfunction "A8_9") (pintype "input"))
      (node (ref "IC5") (pin "1") (pinfunction "G1_1") (pintype "input"))
      (node (ref "IC5") (pin "10") (pinfunction "GND_10") (pintype "power_in"))
      (node (ref "IC5") (pin "19") (pinfunction "G2_19") (pintype "input"))
      (node (ref "IC5") (pin "2") (pinfunction "A1_2") (pintype "input"))
      (node (ref "IC5") (pin "6") (pinfunction "A5_6") (pintype "input"))
      (node (ref "IC5") (pin "7") (pinfunction "A6_7") (pintype "input"))
      (node (ref "IC5") (pin "8") (pinfunction "A7_8") (pintype "input"))
      (node (ref "IC5") (pin "9") (pinfunction "A8_9") (pintype "input"))
      (node (ref "J1") (pin "2") (pinfunction "2_2") (pintype "passive"))
      (node (ref "JP8") (pin "GND") (pinfunction "GND_GND") (pintype "bidirectional"))
      (node (ref "JP8") (pin "GNDBREAK") (pinfunction "GNDBREAK_GNDBREAK") (pintype "bidirectional"))
      (node (ref "PWR") (pin "C") (pinfunction "C_C") (pintype "passive"))
      (node (ref "PWR1") (pin "C") (pinfunction "C_C") (pintype "passive"))
      (node (ref "R10") (pin "1") (pinfunction "1_1") (pintype "passive"))
      (node (ref "R5") (pin "2") (pinfunction "2_2") (pintype "passive"))
      (node (ref "R7") (pin "1") (pinfunction "1_1") (pintype "passive"))
      (node (ref "RN1") (pin "7") (pinfunction "2_7") (pintype "passive"))
      (node (ref "RN1") (pin "8") (pinfunction "2_8") (pintype "passive"))
      (node (ref "S2") (pin "1") (pinfunction "1_1") (pintype "passive"))
      (node (ref "S2") (pin "2") (pinfunction "2_2") (pintype "passive"))
      (node (ref "SER1") (pin "1") (pinfunction "1_1") (pintype "passive"))
      (node (ref "SER2") (pin "1") (pinfunction "1_1") (pintype "passive"))
      (node (ref "TFT") (pin "1") (pinfunction "1_1") (pintype "passive"))
      (node (ref "TFT") (pin "10") (pinfunction "10_10") (pintype "passive"))
      (node (ref "TFT") (pin "12") (pinfunction "12_12") (pintype "passive"))
      (node (ref "TFT") (pin "14") (pinfunction "14_14") (pintype "passive"))
      (node (ref "TFT") (pin "16") (pinfunction "16_16") (pintype "passive"))
      (node (ref "TFT") (pin "2") (pinfunction "2_2") (pintype "passive"))
      (node (ref "TFT") (pin "4") (pinfunction "4_4") (pintype "passive"))
      (node (ref "TFT") (pin "6") (pinfunction "6_6") (pintype "passive"))
      (node (ref "TFT") (pin "8") (pinfunction "8_8") (pintype "passive"))
      (node (ref "U$1") (pin "GND") (pinfunction "GND_GND") (pintype "power_in"))
      (node (ref "U$1") (pin "GND@0") (pinfunction "GND_GND@0") (pintype "power_in"))
      (node (ref "U$6") (pin "GND") (pinfunction "GND_GND") (pintype "power_in"))
      (node (ref "U$6") (pin "GND@0") (pinfunction "GND_GND@0") (pintype "power_in"))
      (node (ref "U$7") (pin "GND") (pinfunction "GND_GND") (pintype "power_in"))
      (node (ref "U$7") (pin "GND@0") (pinfunction "GND_GND@0") (pintype "power_in"))
      (node (ref "U1") (pin "GND@0") (pinfunction "GND_GND@0") (pintype "power_in"))
      (node (ref "U1") (pin "GND@1") (pinfunction "GND_GND@1") (pintype "power_in"))
      (node (ref "U1") (pin "GND@2") (pinfunction "GND_GND@2") (pintype "power_in"))
      (node (ref "U1") (pin "GND@3") (pinfunction "GND_GND@3") (pintype "power_in"))
      (node (ref "U1") (pin "GND@4") (pinfunction "GND_GND@4") (pintype "power_in"))
      (node (ref "X-MAX") (pin "1") (pinfunction "1_1") (pintype "passive"))
      (node (ref "X-MIN") (pin "1") (pinfunction "1_1") (pintype "passive"))
      (node (ref "Y-MAX") (pin "1") (pinfunction "1_1") (pintype "passive"))
      (node (ref "Y-MIN") (pin "1") (pinfunction "1_1") (pintype "passive"))
    )
    (net (code "100") (name "Net-(A-MOT1-Pad1)") (class "Default")
      (node (ref "A-MOT1") (pin "1") (pinfunction "1_1") (pintype "bidirectional"))
      (node (ref "A-MOT2") (pin "1") (pinfunction "1_1") (pintype "passive"))
      (node (ref "U$1") (pin "2B") (pinfunction "2B_2B") (pintype "output"))
    )
    (net (code "101") (name "Net-(A-MOT1-Pad2)") (class "Default")
      (node (ref "A-MOT1") (pin "2") (pinfunction "2_2") (pintype "bidirectional"))
      (node (ref "A-MOT2") (pin "2") (pinfunction "2_2") (pintype "passive"))
      (node (ref "U$1") (pin "2A") (pinfunction "2A_2A") (pintype "output"))
    )
    (net (code "102") (name "Net-(A-MOT1-Pad3)") (class "Default")
      (node (ref "A-MOT1") (pin "3") (pinfunction "3_3") (pintype "bidirectional"))
      (node (ref "A-MOT2") (pin "3") (pinfunction "3_3") (pintype "passive"))
      (node (ref "U$1") (pin "1A") (pinfunction "1A_1A") (pintype "output"))
    )
    (net (code "103") (name "Net-(A-MOT1-Pad4)") (class "Default")
      (node (ref "A-MOT1") (pin "4") (pinfunction "4_4") (pintype "bidirectional"))
      (node (ref "A-MOT2") (pin "4") (pinfunction "4_4") (pintype "passive"))
      (node (ref "U$1") (pin "1B") (pinfunction "1B_1B") (pintype "output"))
    )
    (net (code "104") (name "Net-(B-MOT1-Pad1)") (class "Default")
      (node (ref "B-MOT1") (pin "1") (pinfunction "1_1") (pintype "bidirectional"))
      (node (ref "B-MOT2") (pin "1") (pinfunction "1_1") (pintype "passive"))
      (node (ref "U$7") (pin "2B") (pinfunction "2B_2B") (pintype "output"))
    )
    (net (code "105") (name "Net-(B-MOT1-Pad2)") (class "Default")
      (node (ref "B-MOT1") (pin "2") (pinfunction "2_2") (pintype "bidirectional"))
      (node (ref "B-MOT2") (pin "2") (pinfunction "2_2") (pintype "passive"))
      (node (ref "U$7") (pin "2A") (pinfunction "2A_2A") (pintype "output"))
    )
    (net (code "106") (name "Net-(B-MOT1-Pad3)") (class "Default")
      (node (ref "B-MOT1") (pin "3") (pinfunction "3_3") (pintype "bidirectional"))
      (node (ref "B-MOT2") (pin "3") (pinfunction "3_3") (pintype "passive"))
      (node (ref "U$7") (pin "1A") (pinfunction "1A_1A") (pintype "output"))
    )
    (net (code "107") (name "Net-(B-MOT1-Pad4)") (class "Default")
      (node (ref "B-MOT1") (pin "4") (pinfunction "4_4") (pintype "bidirectional"))
      (node (ref "B-MOT2") (pin "4") (pinfunction "4_4") (pintype "passive"))
      (node (ref "U$7") (pin "1B") (pinfunction "1B_1B") (pintype "output"))
    )
    (net (code "108") (name "Net-(C-MOT1-Pad1)") (class "Default")
      (node (ref "C-MOT1") (pin "1") (pinfunction "1_1") (pintype "bidirectional"))
      (node (ref "C-MOT2") (pin "1") (pinfunction "1_1") (pintype "passive"))
      (node (ref "U$6") (pin "2B") (pinfunction "2B_2B") (pintype "output"))
    )
    (net (code "109") (name "Net-(C-MOT1-Pad2)") (class "Default")
      (node (ref "C-MOT1") (pin "2") (pinfunction "2_2") (pintype "bidirectional"))
      (node (ref "C-MOT2") (pin "2") (pinfunction "2_2") (pintype "passive"))
      (node (ref "U$6") (pin "2A") (pinfunction "2A_2A") (pintype "output"))
    )
    (net (code "110") (name "Net-(C-MOT1-Pad3)") (class "Default")
      (node (ref "C-MOT1") (pin "3") (pinfunction "3_3") (pintype "bidirectional"))
      (node (ref "C-MOT2") (pin "3") (pinfunction "3_3") (pintype "passive"))
      (node (ref "U$6") (pin "1A") (pinfunction "1A_1A") (pintype "output"))
    )
    (net (code "111") (name "Net-(C-MOT1-Pad4)") (class "Default")
      (node (ref "C-MOT1") (pin "4") (pinfunction "4_4") (pintype "bidirectional"))
      (node (ref "C-MOT2") (pin "4") (pinfunction "4_4") (pintype "passive"))
      (node (ref "U$6") (pin "1B") (pinfunction "1B_1B") (pintype "output"))
    )
    (net (code "112") (name "Net-(C5-Pad1)") (class "Default")
      (node (ref "C5") (pin "1") (pinfunction "1_1") (pintype "passive"))
      (node (ref "IC1") (pin "COMP") (pinfunction "COMP_COMP") (pintype "bidirectional"))
    )
    (net (code "113") (name "Net-(C5-Pad2)") (class "Default")
      (node (ref "C5") (pin "2") (pinfunction "2_2") (pintype "passive"))
      (node (ref "R7") (pin "2") (pinfunction "2_2") (pintype "passive"))
    )
    (net (code "114") (name "Net-(C8-Pad1)") (class "Default")
      (node (ref "C8") (pin "1") (pinfunction "1_1") (pintype "passive"))
      (node (ref "IC1") (pin "BS") (pinfunction "BS_BS") (pintype "bidirectional"))
    )
    (net (code "115") (name "Net-(C8-Pad2)") (class "Default")
      (node (ref "C8") (pin "2") (pinfunction "2_2") (pintype "passive"))
      (node (ref "IC1") (pin "SW") (pinfunction "SW_SW") (pintype "bidirectional"))
      (node (ref "L1") (pin "1") (pinfunction "1_1") (pintype "passive"))
    )
    (net (code "116") (name "Net-(C9-Pad1)") (class "Default")
      (node (ref "C9") (pin "1") (pinfunction "1_1") (pintype "passive"))
      (node (ref "IC1") (pin "SS") (pinfunction "SS_SS") (pintype "bidirectional"))
    )
    (net (code "117") (name "Net-(C12-Pad+)") (class "Default")
      (node (ref "C12") (pin "+") (pinfunction "+_+") (pintype "passive"))
      (node (ref "C7") (pin "1") (pinfunction "1_1") (pintype "passive"))
      (node (ref "D2") (pin "A") (pinfunction "A_A") (pintype "passive"))
      (node (ref "L1") (pin "2") (pinfunction "2_2") (pintype "passive"))
      (node (ref "ON_BOARD_PWR") (pin "1") (pinfunction "1_1") (pintype "passive"))
      (node (ref "ON_BOARD_PWR") (pin "2") (pinfunction "2_2") (pintype "passive"))
      (node (ref "R12") (pin "1") (pinfunction "1_1") (pintype "passive"))
      (node (ref "R9") (pin "2") (pinfunction "2_2") (pintype "passive"))
    )
    (net (code "118") (name "Net-(C_STP-PadA)") (class "Default")
      (node (ref "C_STP") (pin "A") (pinfunction "A_A") (pintype "passive"))
      (node (ref "R3") (pin "1") (pinfunction "1_1") (pintype "passive"))
    )
    (net (code "119") (name "Net-(D13-PadA)") (class "Default")
      (node (ref "D13") (pin "A") (pinfunction "A_A") (pintype "passive"))
      (node (ref "RN2") (pin "1") (pinfunction "1_1") (pintype "passive"))
    )
    (net (code "120") (name "Net-(IC1-PadEN)") (class "Default")
      (node (ref "IC1") (pin "EN") (pinfunction "EN_EN") (pintype "bidirectional"))
      (node (ref "R4") (pin "2") (pinfunction "2_2") (pintype "passive"))
    )
    (net (code "121") (name "Net-(IC1-PadFB)") (class "Default")
      (node (ref "IC1") (pin "FB") (pinfunction "FB_FB") (pintype "bidirectional"))
      (node (ref "R10") (pin "2") (pinfunction "2_2") (pintype "passive"))
      (node (ref "R9") (pin "1") (pinfunction "1_1") (pintype "passive"))
    )
    (net (code "122") (name "Net-(PWR1-PadA)") (class "Default")
      (node (ref "PWR1") (pin "A") (pinfunction "A_A") (pintype "passive"))
      (node (ref "R12") (pin "2") (pinfunction "2_2") (pintype "passive"))
    )
    (net (code "123") (name "Net-(R5-Pad1)") (class "Default")
      (node (ref "R5") (pin "1") (pinfunction "1_1") (pintype "passive"))
      (node (ref "SJ1") (pin "2") (pinfunction "2_2") (pintype "passive"))
      (node (ref "U$6") (pin "MS1") (pinfunction "MS1_MS1") (pintype "input"))
    )
    (net (code "124") (name "Net-(RN1-Pad1)") (class "Default")
      (node (ref "RN1") (pin "1") (pinfunction "1_1") (pintype "passive"))
      (node (ref "SJ7") (pin "2") (pinfunction "2_2") (pintype "passive"))
      (node (ref "U$1") (pin "MS1") (pinfunction "MS1_MS1") (pintype "input"))
    )
    (net (code "125") (name "Net-(RN1B-1)") (class "Default")
      (node (ref "RN1") (pin "2") (pinfunction "1_2") (pintype "passive"))
      (node (ref "SJ3") (pin "2") (pinfunction "2_2") (pintype "passive"))
      (node (ref "U$7") (pin "MS1") (pinfunction "MS1_MS1") (pintype "input"))
    )
    (net (code "126") (name "Net-(RN1C-2)") (class "Default")
      (node (ref "A_STP") (pin "A") (pinfunction "A_A") (pintype "passive"))
      (node (ref "RN1") (pin "6") (pinfunction "2_6") (pintype "passive"))
    )
    (net (code "127") (name "Net-(RN1D-2)") (class "Default")
      (node (ref "B_STP") (pin "A") (pinfunction "A_A") (pintype "passive"))
      (node (ref "RN1") (pin "5") (pinfunction "2_5") (pintype "passive"))
    )
    (net (code "128") (name "Net-(RN2B-1)") (class "Default")
      (node (ref "RN2") (pin "2") (pinfunction "1_2") (pintype "passive"))
      (node (ref "RX_LED") (pin "C") (pinfunction "C_C") (pintype "passive"))
    )
    (net (code "129") (name "Net-(RN2C-1)") (class "Default")
      (node (ref "RN2") (pin "3") (pinfunction "1_3") (pintype "passive"))
      (node (ref "TX_LED") (pin "C") (pinfunction "C_C") (pintype "passive"))
    )
    (net (code "130") (name "Net-(RN2D-1)") (class "Default")
      (node (ref "PWR") (pin "A") (pinfunction "A_A") (pintype "passive"))
      (node (ref "RN2") (pin "4") (pinfunction "1_4") (pintype "passive"))
    )
    (net (code "131") (name "Net-(SJ2-Pad2)") (class "Default")
      (node (ref "SJ2") (pin "2") (pinfunction "2_2") (pintype "passive"))
      (node (ref "U$6") (pin "MS2") (pinfunction "MS2_MS2") (pintype "input"))
    )
    (net (code "132") (name "Net-(SJ4-Pad2)") (class "Default")
      (node (ref "SJ4") (pin "2") (pinfunction "2_2") (pintype "passive"))
      (node (ref "U$7") (pin "MS2") (pinfunction "MS2_MS2") (pintype "input"))
    )
    (net (code "133") (name "Net-(SJ5-Pad2)") (class "Default")
      (node (ref "SJ5") (pin "2") (pinfunction "2_2") (pintype "passive"))
      (node (ref "U$6") (pin "MS3") (pinfunction "MS3_MS3") (pintype "input"))
    )
    (net (code "134") (name "Net-(SJ6-Pad2)") (class "Default")
      (node (ref "SJ6") (pin "2") (pinfunction "2_2") (pintype "passive"))
      (node (ref "U$7") (pin "MS3") (pinfunction "MS3_MS3") (pintype "input"))
    )
    (net (code "135") (name "Net-(SJ8-Pad2)") (class "Default")
      (node (ref "SJ8") (pin "2") (pinfunction "2_2") (pintype "passive"))
      (node (ref "U$1") (pin "MS2") (pinfunction "MS2_MS2") (pintype "input"))
    )
    (net (code "136") (name "Net-(SJ9-Pad2)") (class "Default")
      (node (ref "SJ9") (pin "2") (pinfunction "2_2") (pintype "passive"))
      (node (ref "U$1") (pin "MS3") (pinfunction "MS3_MS3") (pintype "input"))
    )
    (net (code "137") (name "Net-(U$1-SLEEP)") (class "Default")
      (node (ref "U$1") (pin "RST") (pinfunction "RST_RST") (pintype "input"))
      (node (ref "U$1") (pin "SLP") (pinfunction "SLEEP_SLP") (pintype "input"))
    )
    (net (code "138") (name "Net-(U$6-SLEEP)") (class "Default")
      (node (ref "U$6") (pin "RST") (pinfunction "RST_RST") (pintype "input"))
      (node (ref "U$6") (pin "SLP") (pinfunction "SLEEP_SLP") (pintype "input"))
    )
    (net (code "139") (name "Net-(U$7-SLEEP)") (class "Default")
      (node (ref "U$7") (pin "RST") (pinfunction "RST_RST") (pintype "input"))
      (node (ref "U$7") (pin "SLP") (pinfunction "SLEEP_SLP") (pintype "input"))
    )
    (net (code "140") (name "VCC") (class "Default")
      (node (ref "D2") (pin "C") (pinfunction "C_C") (pintype "passive"))
      (node (ref "IC5") (pin "20") (pinfunction "VCC_20") (pintype "power_in"))
      (node (ref "R18") (pin "1") (pinfunction "1_1") (pintype "passive"))
      (node (ref "R19") (pin "1") (pinfunction "1_1") (pintype "passive"))
      (node (ref "R2") (pin "1") (pinfunction "1_1") (pintype "passive"))
      (node (ref "RN2") (pin "5") (pinfunction "2_5") (pintype "passive"))
      (node (ref "RX_LED") (pin "A") (pinfunction "A_A") (pintype "passive"))
      (node (ref "SER1") (pin "2") (pinfunction "2_2") (pintype "passive"))
      (node (ref "SER2") (pin "2") (pinfunction "2_2") (pintype "passive"))
      (node (ref "SJ1") (pin "1") (pinfunction "1_1") (pintype "passive"))
      (node (ref "SJ2") (pin "1") (pinfunction "1_1") (pintype "passive"))
      (node (ref "SJ3") (pin "1") (pinfunction "1_1") (pintype "passive"))
      (node (ref "SJ4") (pin "1") (pinfunction "1_1") (pintype "passive"))
      (node (ref "SJ5") (pin "1") (pinfunction "1_1") (pintype "passive"))
      (node (ref "SJ6") (pin "1") (pinfunction "1_1") (pintype "passive"))
      (node (ref "SJ7") (pin "1") (pinfunction "1_1") (pintype "passive"))
      (node (ref "SJ8") (pin "1") (pinfunction "1_1") (pintype "passive"))
      (node (ref "SJ9") (pin "1") (pinfunction "1_1") (pintype "passive"))
      (node (ref "TFT") (pin "3") (pinfunction "3_3") (pintype "passive"))
      (node (ref "TX_LED") (pin "A") (pinfunction "A_A") (pintype "passive"))
      (node (ref "U$1") (pin "VDD") (pinfunction "VDD_VDD") (pintype "power_in"))
      (node (ref "U$6") (pin "VDD") (pinfunction "VDD_VDD") (pintype "power_in"))
      (node (ref "U$7") (pin "VDD") (pinfunction "VDD_VDD") (pintype "power_in"))
      (node (ref "U1") (pin "5V@0") (pinfunction "5V_5V@0") (pintype "power_in"))
      (node (ref "U1") (pin "5V@1") (pinfunction "5V_5V@1") (pintype "power_in"))
      (node (ref "U1") (pin "5V@2") (pinfunction "5V_5V@2") (pintype "power_in"))
      (node (ref "X-MAX") (pin "2") (pinfunction "2_2") (pintype "passive"))
      (node (ref "X-MIN") (pin "2") (pinfunction "2_2") (pintype "passive"))
      (node (ref "Y-MAX") (pin "2") (pinfunction "2_2") (pintype "passive"))
      (node (ref "Y-MIN") (pin "2") (pinfunction "2_2") (pintype "passive"))
    )
    (net (code "141") (name "unconnected-(IC3A-Y3-Pad16)") (class "Default")
      (node (ref "IC3") (pin "16") (pinfunction "Y3_16") (pintype "tri_state"))
    )
    (net (code "142") (name "unconnected-(IC3A-Y4-Pad15)") (class "Default")
      (node (ref "IC3") (pin "15") (pinfunction "Y4_15") (pintype "tri_state"))
    )
    (net (code "143") (name "unconnected-(IC3A-Y5-Pad14)") (class "Default")
      (node (ref "IC3") (pin "14") (pinfunction "Y5_14") (pintype "tri_state"))
    )
    (net (code "144") (name "unconnected-(IC3A-Y6-Pad13)") (class "Default")
      (node (ref "IC3") (pin "13") (pinfunction "Y6_13") (pintype "tri_state"))
    )
    (net (code "145") (name "unconnected-(IC3A-Y8-Pad11)") (class "Default")
      (node (ref "IC3") (pin "11") (pinfunction "Y8_11") (pintype "tri_state"))
    )
    (net (code "146") (name "unconnected-(IC4A-Y8-Pad11)") (class "Default")
      (node (ref "IC4") (pin "11") (pinfunction "Y8_11") (pintype "tri_state"))
    )
    (net (code "147") (name "unconnected-(IC5A-Y1-Pad18)") (class "Default")
      (node (ref "IC5") (pin "18") (pinfunction "Y1_18") (pintype "tri_state"))
    )
    (net (code "148") (name "unconnected-(IC5A-Y5-Pad14)") (class "Default")
      (node (ref "IC5") (pin "14") (pinfunction "Y5_14") (pintype "tri_state"))
    )
    (net (code "149") (name "unconnected-(IC5A-Y6-Pad13)") (class "Default")
      (node (ref "IC5") (pin "13") (pinfunction "Y6_13") (pintype "tri_state"))
    )
    (net (code "150") (name "unconnected-(IC5A-Y7-Pad12)") (class "Default")
      (node (ref "IC5") (pin "12") (pinfunction "Y7_12") (pintype "tri_state"))
    )
    (net (code "151") (name "unconnected-(IC5A-Y8-Pad11)") (class "Default")
      (node (ref "IC5") (pin "11") (pinfunction "Y8_11") (pintype "tri_state"))
    )
    (net (code "152") (name "unconnected-(TFT-Pad5)") (class "Default")
      (node (ref "TFT") (pin "5") (pinfunction "5_5") (pintype "passive"))
    )
    (net (code "153") (name "unconnected-(TFT-Pad24)") (class "Default")
      (node (ref "TFT") (pin "24") (pinfunction "24_24") (pintype "passive"))
    )
    (net (code "154") (name "unconnected-(TFT-Pad31)") (class "Default")
      (node (ref "TFT") (pin "31") (pinfunction "31_31") (pintype "passive"))
    )
    (net (code "155") (name "unconnected-(TFT-Pad35)") (class "Default")
      (node (ref "TFT") (pin "35") (pinfunction "35_35") (pintype "passive"))
    )
    (net (code "156") (name "unconnected-(TFT-Pad38)") (class "Default")
      (node (ref "TFT") (pin "38") (pinfunction "38_38") (pintype "passive"))
    )
    (net (code "157") (name "unconnected-(TFT-Pad39)") (class "Default")
      (node (ref "TFT") (pin "39") (pinfunction "39_39") (pintype "passive"))
    )
    (net (code "158") (name "unconnected-(TFT-Pad40)") (class "Default")
      (node (ref "TFT") (pin "40") (pinfunction "40_40") (pintype "passive"))
    )
  )
)
